# 11_WIFI_L-NLODB37.net
KiCad netlist of a schematic drawn in Altium Designer
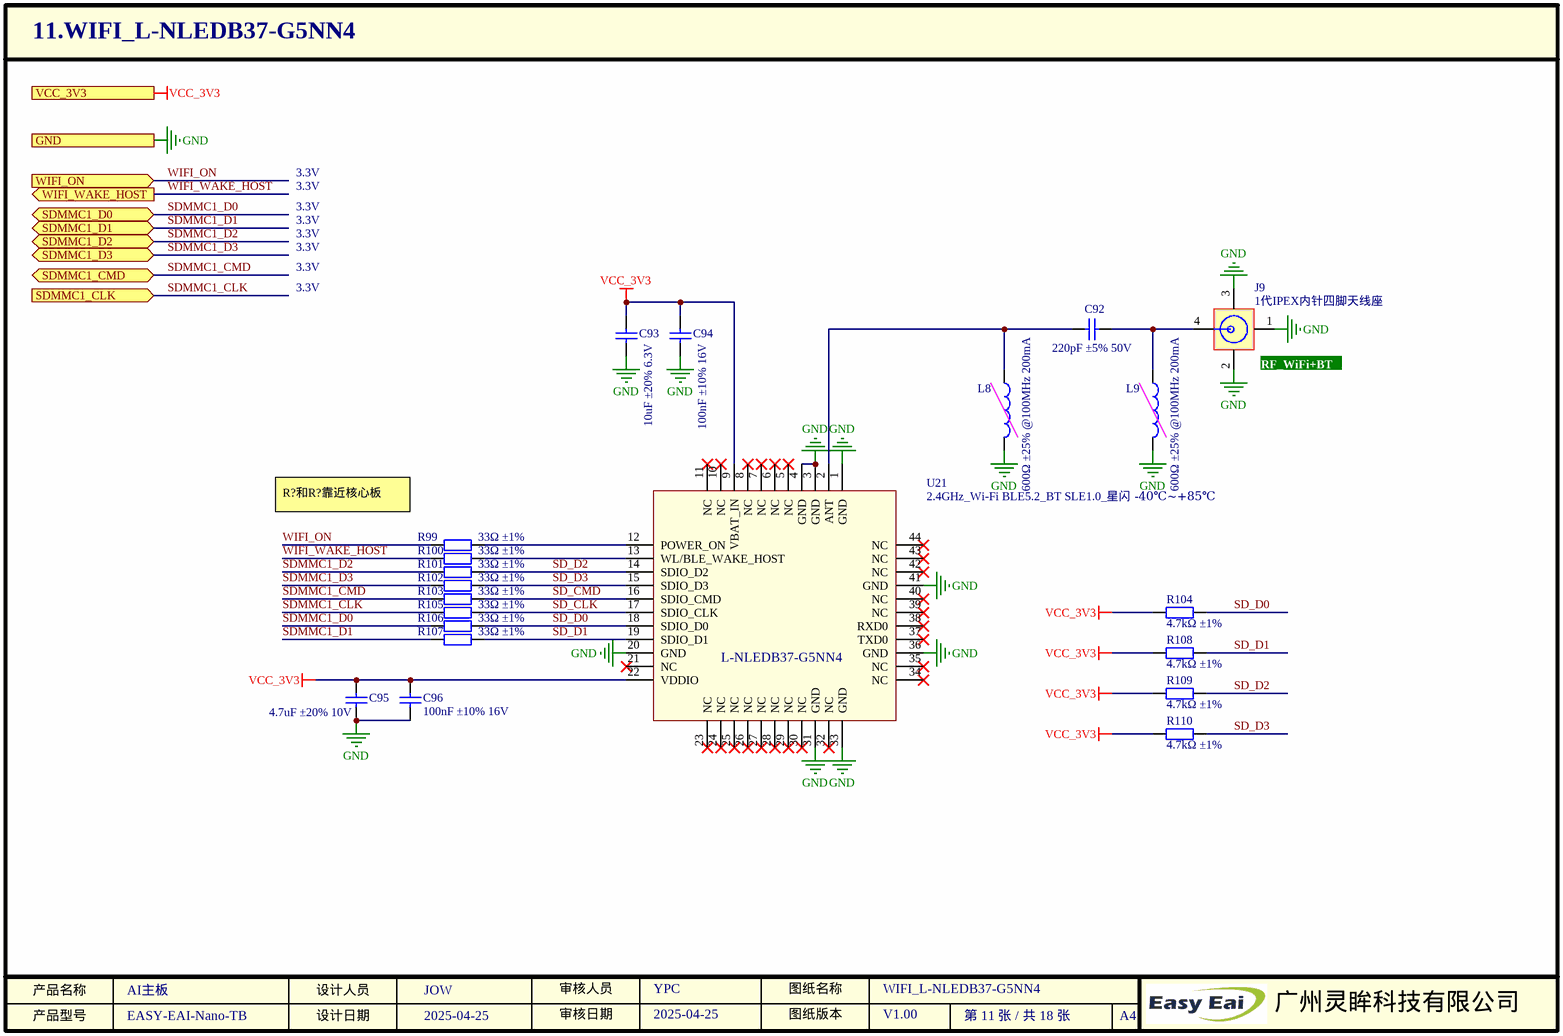
[diagram p0: 11.WIFI_L-NLODB37.SchDoc]

(export (version "E")
  (design (tool "Eeschema 10.0.6"))
  (components
    (comp (ref "C92")
      (value "GCM1555G1H221JA16D")
      (footprint "0402_C")
      (description "SPZL000318")
      (fields (field (name "描述") "220pF ±5% 50V"))
      (libsource (lib "CAP_EASY-EAI") (part "0402 220pF ±5% 50V"))
    )
    (comp (ref "C93")
      (value "CL05A106MQ5NUNC")
      (footprint "0402_C")
      (description "SPZL000269")
      (fields (field (name "描述") "10uF ±20% 6.3V"))
      (libsource (lib "altium-import") (part "root_1_0402 10uF ±20% 6.3V_"))
    )
    (comp (ref "C94")
      (value "CL05B104KO5NNNC")
      (footprint "0402_C")
      (description "SPZL000259")
      (fields (field (name "描述") "100nF ±10% 16V"))
      (libsource (lib "altium-import") (part "root_1_0402 100nF ±10% 16V_"))
    )
    (comp (ref "C95")
      (value "CL05A475MP5NRNC")
      (footprint "0402_C")
      (description "SPZL000339")
      (fields (field (name "描述") "4.7uF ±20% 10V"))
      (libsource (lib "altium-import") (part "root_1_0402 4.7uF ±20% 10V_"))
    )
    (comp (ref "C96")
      (value "CL05B104KO5NNNC")
      (footprint "0402_C")
      (description "SPZL000259")
      (fields (field (name "描述") "100nF ±10% 16V"))
      (libsource (lib "altium-import") (part "root_1_0402 100nF ±10% 16V_"))
    )
    (comp (ref "J9")
      (value "KH-IPEX-K501-29")
      (footprint "ANT-SMD_KH-IPEX-K501-29")
      (description "SPZL001156")
      (fields (field (name "描述") "1代IPEX内针四脚天线座"))
      (libsource (lib "Connector_EASY-EAI") (part "1代IPEX内针四脚天线座"))
    )
    (comp (ref "L8")
      (value "CBW100505U601T")
      (footprint "0402_R")
      (description "SPZL000058")
      (fields (field (name "描述") "600Ω ±25% @100MHz 200mA"))
      (libsource (lib "altium-import") (part "root_0_600Ω ±25% @100MHz 200mA_"))
    )
    (comp (ref "L9")
      (value "CBW100505U601T")
      (footprint "0402_R")
      (description "SPZL000058")
      (fields (field (name "描述") "600Ω ±25% @100MHz 200mA"))
      (libsource (lib "altium-import") (part "root_0_600Ω ±25% @100MHz 200mA_"))
    )
    (comp (ref "R99")
      (value "RC-02W33R0FT")
      (footprint "0402_R")
      (description "SPZL000302")
      (fields (field (name "描述") "33Ω ±1%"))
      (libsource (lib "RES_EASY-EAI") (part "0402 33Ω ±1%"))
    )
    (comp (ref "R100")
      (value "RC-02W33R0FT")
      (footprint "0402_R")
      (description "SPZL000302")
      (fields (field (name "描述") "33Ω ±1%"))
      (libsource (lib "RES_EASY-EAI") (part "0402 33Ω ±1%"))
    )
    (comp (ref "R101")
      (value "RC-02W33R0FT")
      (footprint "0402_R")
      (description "SPZL000302")
      (fields (field (name "描述") "33Ω ±1%"))
      (libsource (lib "RES_EASY-EAI") (part "0402 33Ω ±1%"))
    )
    (comp (ref "R102")
      (value "RC-02W33R0FT")
      (footprint "0402_R")
      (description "SPZL000302")
      (fields (field (name "描述") "33Ω ±1%"))
      (libsource (lib "RES_EASY-EAI") (part "0402 33Ω ±1%"))
    )
    (comp (ref "R103")
      (value "RC-02W33R0FT")
      (footprint "0402_R")
      (description "SPZL000302")
      (fields (field (name "描述") "33Ω ±1%"))
      (libsource (lib "RES_EASY-EAI") (part "0402 33Ω ±1%"))
    )
    (comp (ref "R104")
      (value "0402WGF4701TCE")
      (footprint "0402_R")
      (description "SPZL000280")
      (fields (field (name "描述") "4.7kΩ ±1%"))
      (libsource (lib "RES_EASY-EAI") (part "0402 4.7kΩ ±1%"))
    )
    (comp (ref "R105")
      (value "RC-02W33R0FT")
      (footprint "0402_R")
      (description "SPZL000302")
      (fields (field (name "描述") "33Ω ±1%"))
      (libsource (lib "RES_EASY-EAI") (part "0402 33Ω ±1%"))
    )
    (comp (ref "R106")
      (value "RC-02W33R0FT")
      (footprint "0402_R")
      (description "SPZL000302")
      (fields (field (name "描述") "33Ω ±1%"))
      (libsource (lib "RES_EASY-EAI") (part "0402 33Ω ±1%"))
    )
    (comp (ref "R107")
      (value "RC-02W33R0FT")
      (footprint "0402_R")
      (description "SPZL000302")
      (fields (field (name "描述") "33Ω ±1%"))
      (libsource (lib "RES_EASY-EAI") (part "0402 33Ω ±1%"))
    )
    (comp (ref "R108")
      (value "0402WGF4701TCE")
      (footprint "0402_R")
      (description "SPZL000280")
      (fields (field (name "描述") "4.7kΩ ±1%"))
      (libsource (lib "RES_EASY-EAI") (part "0402 4.7kΩ ±1%"))
    )
    (comp (ref "R109")
      (value "0402WGF4701TCE")
      (footprint "0402_R")
      (description "SPZL000280")
      (fields (field (name "描述") "4.7kΩ ±1%"))
      (libsource (lib "RES_EASY-EAI") (part "0402 4.7kΩ ±1%"))
    )
    (comp (ref "R110")
      (value "0402WGF4701TCE")
      (footprint "0402_R")
      (description "SPZL000280")
      (fields (field (name "描述") "4.7kΩ ±1%"))
      (libsource (lib "RES_EASY-EAI") (part "0402 4.7kΩ ±1%"))
    )
    (comp (ref "U21")
      (value "L-NLEDB37-G5NN4")
      (footprint "L-NLEDB37-G5NN4_SMT")
      (description "SPZL001091")
      (fields (field (name "描述") "2.4GHz_Wi-Fi BLE5.2_BT SLE1.0_星闪 -40℃~+85℃"))
      (libsource (lib "IC_EASY-EAI") (part "L-NLEDB37-G5NN4"))
    )
  )
  (nets
    (net (code "1") (name "/SDMMC1_CLK") (class "Default")
      (node (ref "R105") (pin "1") (pinfunction "1_1") (pintype "passive"))
    )
    (net (code "2") (name "/SDMMC1_CMD") (class "Default")
      (node (ref "R103") (pin "1") (pinfunction "1_1") (pintype "passive"))
    )
    (net (code "3") (name "/SDMMC1_D0") (class "Default")
      (node (ref "R106") (pin "1") (pinfunction "1_1") (pintype "passive"))
    )
    (net (code "4") (name "/SDMMC1_D1") (class "Default")
      (node (ref "R107") (pin "1") (pinfunction "1_1") (pintype "passive"))
    )
    (net (code "5") (name "/SDMMC1_D2") (class "Default")
      (node (ref "R101") (pin "1") (pinfunction "1_1") (pintype "passive"))
    )
    (net (code "6") (name "/SDMMC1_D3") (class "Default")
      (node (ref "R102") (pin "1") (pinfunction "1_1") (pintype "passive"))
    )
    (net (code "7") (name "/SD_CLK") (class "Default")
      (node (ref "R105") (pin "2") (pinfunction "2_2") (pintype "passive"))
      (node (ref "U21") (pin "17") (pinfunction "SDIO_CLK_17") (pintype "passive"))
    )
    (net (code "8") (name "/SD_CMD") (class "Default")
      (node (ref "R103") (pin "2") (pinfunction "2_2") (pintype "passive"))
      (node (ref "U21") (pin "16") (pinfunction "SDIO_CMD_16") (pintype "passive"))
    )
    (net (code "9") (name "/SD_D0") (class "Default")
      (node (ref "R104") (pin "2") (pinfunction "2_2") (pintype "passive"))
      (node (ref "R106") (pin "2") (pinfunction "2_2") (pintype "passive"))
      (node (ref "U21") (pin "18") (pinfunction "SDIO_D0_18") (pintype "passive"))
    )
    (net (code "10") (name "/SD_D1") (class "Default")
      (node (ref "R107") (pin "2") (pinfunction "2_2") (pintype "passive"))
      (node (ref "R108") (pin "2") (pinfunction "2_2") (pintype "passive"))
      (node (ref "U21") (pin "19") (pinfunction "SDIO_D1_19") (pintype "passive"))
    )
    (net (code "11") (name "/SD_D2") (class "Default")
      (node (ref "R101") (pin "2") (pinfunction "2_2") (pintype "passive"))
      (node (ref "R109") (pin "2") (pinfunction "2_2") (pintype "passive"))
      (node (ref "U21") (pin "14") (pinfunction "SDIO_D2_14") (pintype "passive"))
    )
    (net (code "12") (name "/SD_D3") (class "Default")
      (node (ref "R102") (pin "2") (pinfunction "2_2") (pintype "passive"))
      (node (ref "R110") (pin "2") (pinfunction "2_2") (pintype "passive"))
      (node (ref "U21") (pin "15") (pinfunction "SDIO_D3_15") (pintype "passive"))
    )
    (net (code "13") (name "/WIFI_ON") (class "Default")
      (node (ref "R99") (pin "1") (pinfunction "1_1") (pintype "passive"))
    )
    (net (code "14") (name "/WIFI_WAKE_HOST") (class "Default")
      (node (ref "R100") (pin "1") (pinfunction "1_1") (pintype "passive"))
    )
    (net (code "15") (name "GND") (class "Default")
      (node (ref "C93") (pin "1") (pinfunction "1_1") (pintype "passive"))
      (node (ref "C94") (pin "1") (pinfunction "1_1") (pintype "passive"))
      (node (ref "C95") (pin "1") (pinfunction "1_1") (pintype "passive"))
      (node (ref "C96") (pin "1") (pinfunction "1_1") (pintype "passive"))
      (node (ref "J9") (pin "1") (pinfunction "1_1") (pintype "passive"))
      (node (ref "J9") (pin "2") (pinfunction "2_2") (pintype "passive"))
      (node (ref "J9") (pin "3") (pinfunction "3_3") (pintype "passive"))
      (node (ref "L8") (pin "2") (pinfunction "2_2") (pintype "passive"))
      (node (ref "L9") (pin "2") (pinfunction "2_2") (pintype "passive"))
      (node (ref "U21") (pin "1") (pinfunction "GND_1") (pintype "passive"))
      (node (ref "U21") (pin "20") (pinfunction "GND_20") (pintype "passive"))
      (node (ref "U21") (pin "3") (pinfunction "GND_3") (pintype "passive"))
      (node (ref "U21") (pin "31") (pinfunction "GND_31") (pintype "passive"))
      (node (ref "U21") (pin "33") (pinfunction "GND_33") (pintype "passive"))
      (node (ref "U21") (pin "36") (pinfunction "GND_36") (pintype "passive"))
      (node (ref "U21") (pin "4") (pinfunction "GND_4") (pintype "passive"))
      (node (ref "U21") (pin "41") (pinfunction "GND_41") (pintype "passive"))
    )
    (net (code "16") (name "Net-(C92-Pad2)") (class "Default")
      (node (ref "C92") (pin "2") (pinfunction "2_2") (pintype "passive"))
      (node (ref "J9") (pin "4") (pinfunction "4_4") (pintype "passive"))
      (node (ref "L9") (pin "1") (pinfunction "1_1") (pintype "passive"))
    )
    (net (code "17") (name "Net-(U21-ANT)") (class "Default")
      (node (ref "C92") (pin "1") (pinfunction "1_1") (pintype "passive"))
      (node (ref "L8") (pin "1") (pinfunction "1_1") (pintype "passive"))
      (node (ref "U21") (pin "2") (pinfunction "ANT_2") (pintype "passive"))
    )
    (net (code "18") (name "Net-(U21-POWER_ON)") (class "Default")
      (node (ref "R99") (pin "2") (pinfunction "2_2") (pintype "passive"))
      (node (ref "U21") (pin "12") (pinfunction "POWER_ON_12") (pintype "passive"))
    )
    (net (code "19") (name "Net-(U21-WL{slash}BLE_WAKE_HOST)") (class "Default")
      (node (ref "R100") (pin "2") (pinfunction "2_2") (pintype "passive"))
      (node (ref "U21") (pin "13") (pinfunction "WL/BLE_WAKE_HOST_13") (pintype "passive"))
    )
    (net (code "20") (name "VCC_3V3") (class "Default")
      (node (ref "C93") (pin "2") (pinfunction "2_2") (pintype "passive"))
      (node (ref "C94") (pin "2") (pinfunction "2_2") (pintype "passive"))
      (node (ref "C95") (pin "2") (pinfunction "2_2") (pintype "passive"))
      (node (ref "C96") (pin "2") (pinfunction "2_2") (pintype "passive"))
      (node (ref "R104") (pin "1") (pinfunction "1_1") (pintype "passive"))
      (node (ref "R108") (pin "1") (pinfunction "1_1") (pintype "passive"))
      (node (ref "R109") (pin "1") (pinfunction "1_1") (pintype "passive"))
      (node (ref "R110") (pin "1") (pinfunction "1_1") (pintype "passive"))
      (node (ref "U21") (pin "22") (pinfunction "VDDIO_22") (pintype "passive"))
      (node (ref "U21") (pin "9") (pinfunction "VBAT_IN_9") (pintype "passive"))
    )
    (net (code "21") (name "unconnected-(U21-NC-Pad5)") (class "Default")
      (node (ref "U21") (pin "5") (pinfunction "NC_5") (pintype "passive+no_connect"))
    )
    (net (code "22") (name "unconnected-(U21-NC-Pad6)") (class "Default")
      (node (ref "U21") (pin "6") (pinfunction "NC_6") (pintype "passive+no_connect"))
    )
    (net (code "23") (name "unconnected-(U21-NC-Pad7)") (class "Default")
      (node (ref "U21") (pin "7") (pinfunction "NC_7") (pintype "passive+no_connect"))
    )
    (net (code "24") (name "unconnected-(U21-NC-Pad8)") (class "Default")
      (node (ref "U21") (pin "8") (pinfunction "NC_8") (pintype "passive+no_connect"))
    )
    (net (code "25") (name "unconnected-(U21-NC-Pad10)") (class "Default")
      (node (ref "U21") (pin "10") (pinfunction "NC_10") (pintype "passive+no_connect"))
    )
    (net (code "26") (name "unconnected-(U21-NC-Pad11)") (class "Default")
      (node (ref "U21") (pin "11") (pinfunction "NC_11") (pintype "passive+no_connect"))
    )
    (net (code "27") (name "unconnected-(U21-NC-Pad21)") (class "Default")
      (node (ref "U21") (pin "21") (pinfunction "NC_21") (pintype "passive+no_connect"))
    )
    (net (code "28") (name "unconnected-(U21-NC-Pad23)") (class "Default")
      (node (ref "U21") (pin "23") (pinfunction "NC_23") (pintype "passive+no_connect"))
    )
    (net (code "29") (name "unconnected-(U21-NC-Pad24)") (class "Default")
      (node (ref "U21") (pin "24") (pinfunction "NC_24") (pintype "passive+no_connect"))
    )
    (net (code "30") (name "unconnected-(U21-NC-Pad25)") (class "Default")
      (node (ref "U21") (pin "25") (pinfunction "NC_25") (pintype "passive+no_connect"))
    )
    (net (code "31") (name "unconnected-(U21-NC-Pad26)") (class "Default")
      (node (ref "U21") (pin "26") (pinfunction "NC_26") (pintype "passive+no_connect"))
    )
    (net (code "32") (name "unconnected-(U21-NC-Pad27)") (class "Default")
      (node (ref "U21") (pin "27") (pinfunction "NC_27") (pintype "passive+no_connect"))
    )
    (net (code "33") (name "unconnected-(U21-NC-Pad28)") (class "Default")
      (node (ref "U21") (pin "28") (pinfunction "NC_28") (pintype "passive+no_connect"))
    )
    (net (code "34") (name "unconnected-(U21-NC-Pad29)") (class "Default")
      (node (ref "U21") (pin "29") (pinfunction "NC_29") (pintype "passive+no_connect"))
    )
    (net (code "35") (name "unconnected-(U21-NC-Pad30)") (class "Default")
      (node (ref "U21") (pin "30") (pinfunction "NC_30") (pintype "passive+no_connect"))
    )
    (net (code "36") (name "unconnected-(U21-NC-Pad32)") (class "Default")
      (node (ref "U21") (pin "32") (pinfunction "NC_32") (pintype "passive+no_connect"))
    )
    (net (code "37") (name "unconnected-(U21-NC-Pad34)") (class "Default")
      (node (ref "U21") (pin "34") (pinfunction "NC_34") (pintype "passive+no_connect"))
    )
    (net (code "38") (name "unconnected-(U21-NC-Pad35)") (class "Default")
      (node (ref "U21") (pin "35") (pinfunction "NC_35") (pintype "passive+no_connect"))
    )
    (net (code "39") (name "unconnected-(U21-NC-Pad39)") (class "Default")
      (node (ref "U21") (pin "39") (pinfunction "NC_39") (pintype "passive+no_connect"))
    )
    (net (code "40") (name "unconnected-(U21-NC-Pad40)") (class "Default")
      (node (ref "U21") (pin "40") (pinfunction "NC_40") (pintype "passive+no_connect"))
    )
    (net (code "41") (name "unconnected-(U21-NC-Pad42)") (class "Default")
      (node (ref "U21") (pin "42") (pinfunction "NC_42") (pintype "passive+no_connect"))
    )
    (net (code "42") (name "unconnected-(U21-NC-Pad43)") (class "Default")
      (node (ref "U21") (pin "43") (pinfunction "NC_43") (pintype "passive+no_connect"))
    )
    (net (code "43") (name "unconnected-(U21-NC-Pad44)") (class "Default")
      (node (ref "U21") (pin "44") (pinfunction "NC_44") (pintype "passive+no_connect"))
    )
    (net (code "44") (name "unconnected-(U21-RXD0-Pad38)") (class "Default")
      (node (ref "U21") (pin "38") (pinfunction "RXD0_38") (pintype "passive+no_connect"))
    )
    (net (code "45") (name "unconnected-(U21-TXD0-Pad37)") (class "Default")
      (node (ref "U21") (pin "37") (pinfunction "TXD0_37") (pintype "passive+no_connect"))
    )
  )
)
